# Sheet1.net
KiCad netlist of a schematic drawn in Altium Designer
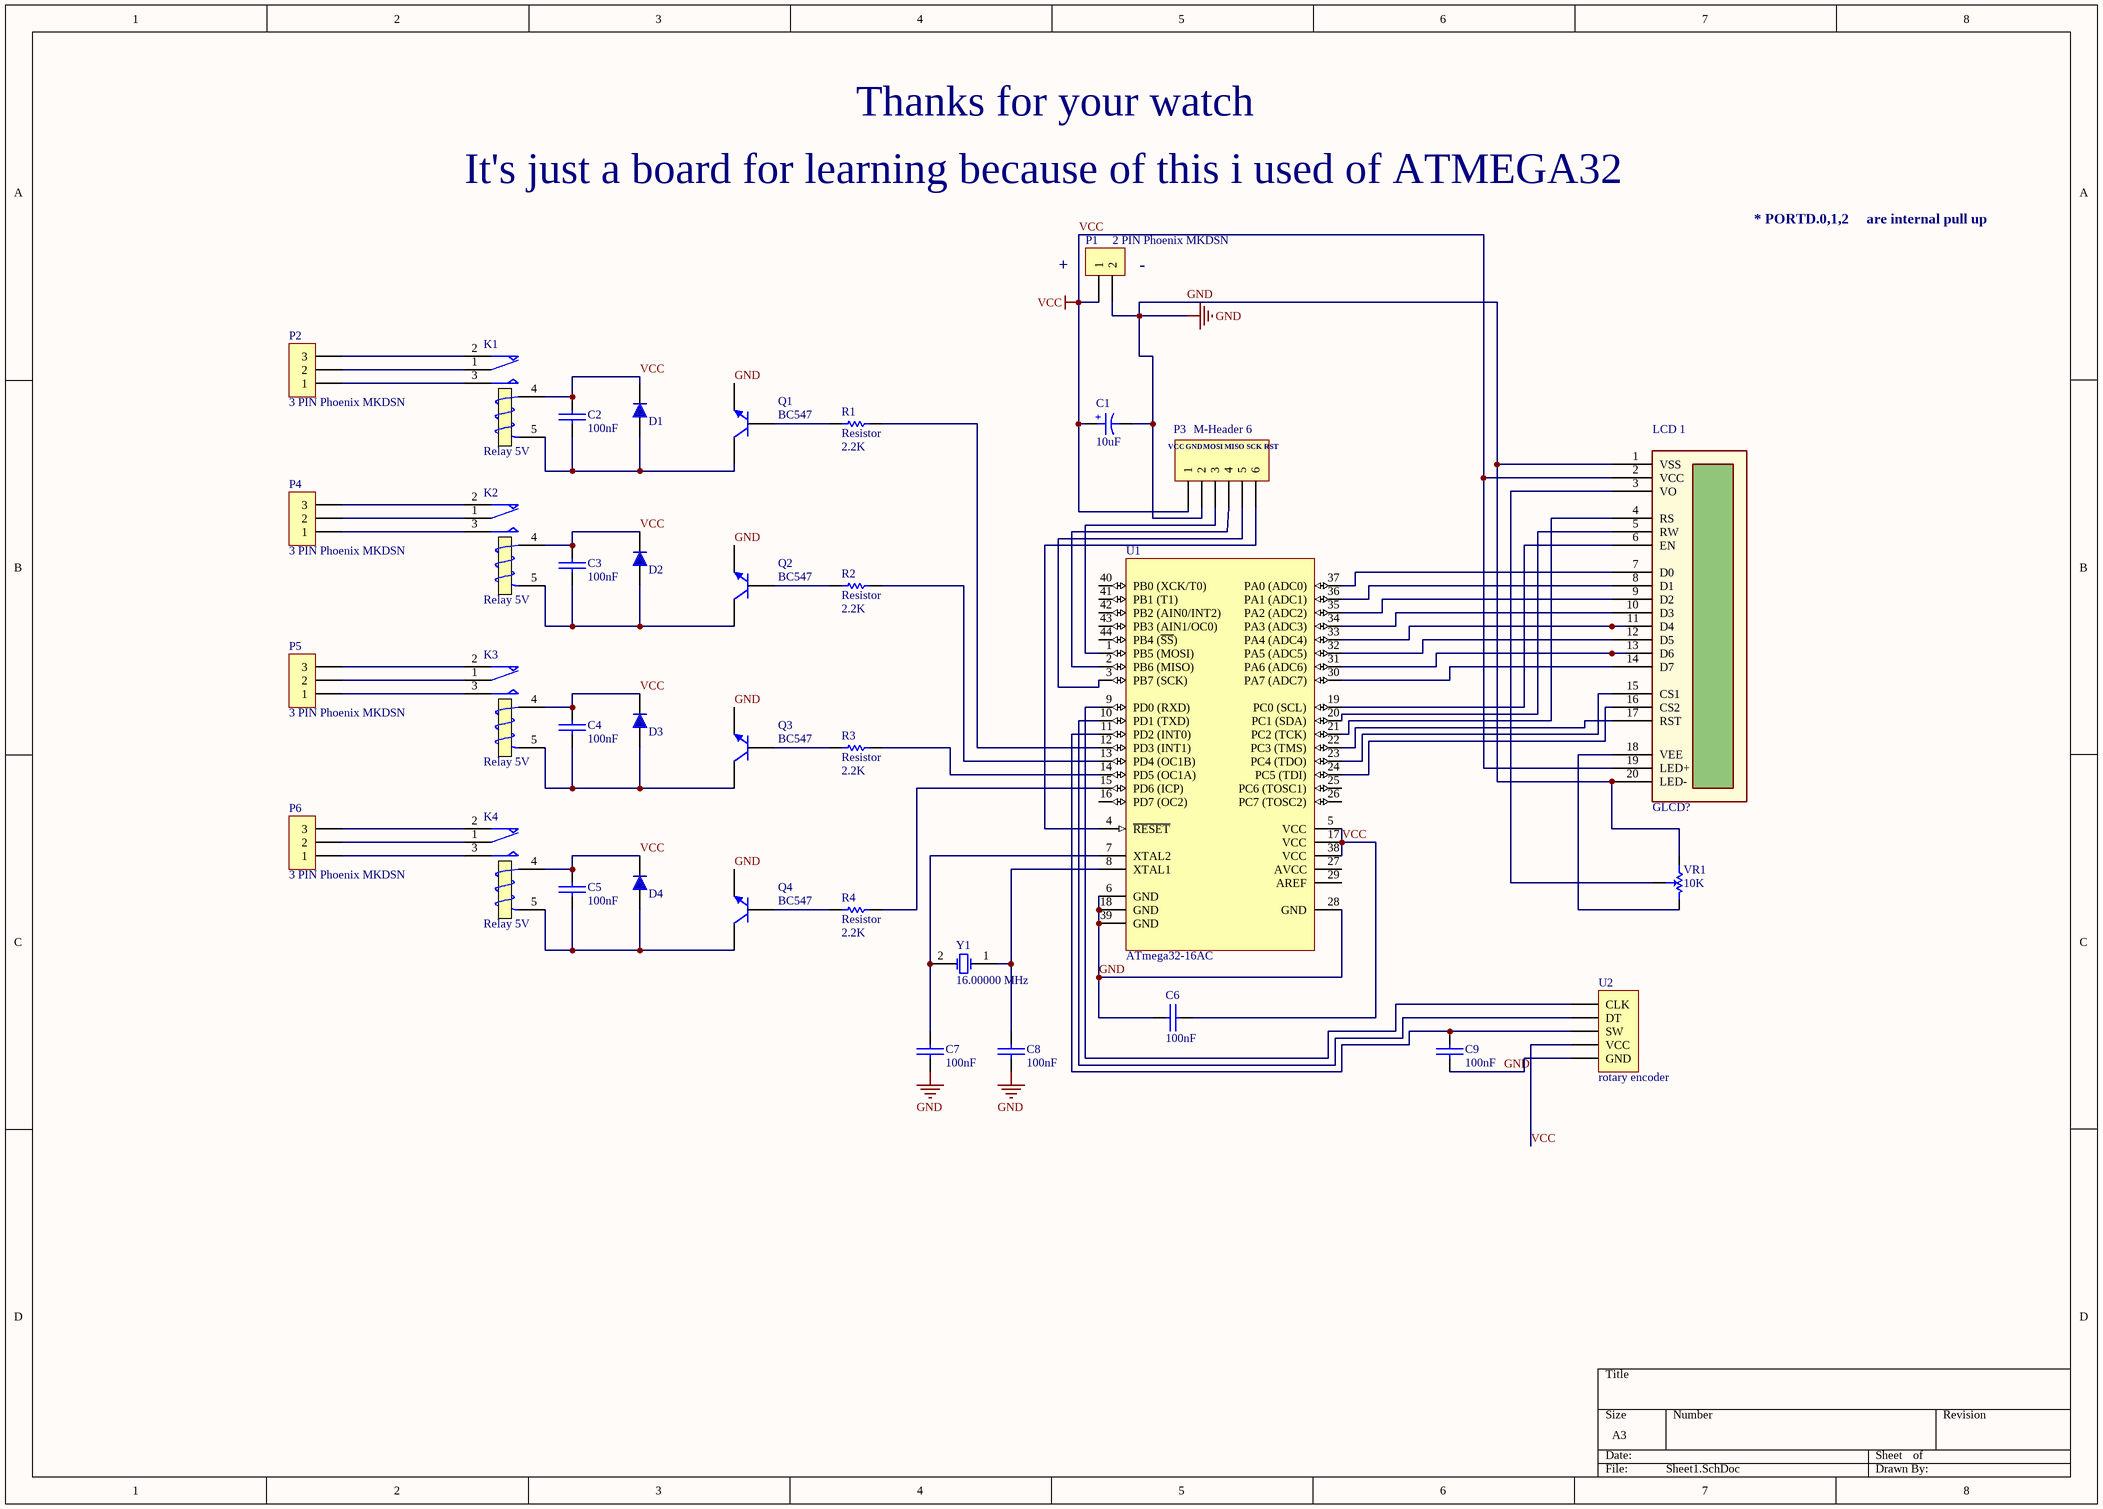
[diagram p0: Sheet1.SchDoc]

(export (version "E")
  (design (tool "Eeschema 10.0.6"))
  (components
    (comp (ref "C1")
      (value "10uF")
      (footprint "Cap 12.5x25-5")
      (description "Capacitor DIP")
      (libsource (lib "Inactive components") (part "Capacitor DIP"))
    )
    (comp (ref "C2")
      (value "100nF")
      (footprint "Cap - 100nF")
      (description "Bipolar Capacitor")
      (fields (field (name "VOLTAGE") "100V") (field (name "DESIGNER") "Saeid Jorablo"))
      (libsource (lib "My_Library") (part "Cap-Bipolar"))
    )
    (comp (ref "C3")
      (value "100nF")
      (footprint "Cap - 100nF")
      (description "Bipolar Capacitor")
      (fields (field (name "VOLTAGE") "100V") (field (name "DESIGNER") "Saeid Jorablo"))
      (libsource (lib "My_Library") (part "Cap-Bipolar"))
    )
    (comp (ref "C4")
      (value "100nF")
      (footprint "Cap - 100nF")
      (description "Bipolar Capacitor")
      (fields (field (name "VOLTAGE") "100V") (field (name "DESIGNER") "Saeid Jorablo"))
      (libsource (lib "My_Library") (part "Cap-Bipolar"))
    )
    (comp (ref "C5")
      (value "100nF")
      (footprint "Cap - 100nF")
      (description "Bipolar Capacitor")
      (fields (field (name "VOLTAGE") "100V") (field (name "DESIGNER") "Saeid Jorablo"))
      (libsource (lib "My_Library") (part "Cap-Bipolar"))
    )
    (comp (ref "C6")
      (value "100nF")
      (footprint "Cap - 100nF")
      (description "Bipolar Capacitor")
      (fields (field (name "VOLTAGE") "100V") (field (name "DESIGNER") "Saeid Jorablo"))
      (libsource (lib "My_Library") (part "Cap-Bipolar"))
    )
    (comp (ref "C7")
      (value "100nF")
      (footprint "Cap - 100nF")
      (description "Bipolar Capacitor")
      (fields (field (name "VOLTAGE") "100V") (field (name "DESIGNER") "Saeid Jorablo"))
      (libsource (lib "My_Library") (part "Cap-Bipolar"))
    )
    (comp (ref "C8")
      (value "100nF")
      (footprint "Cap - 100nF")
      (description "Bipolar Capacitor")
      (fields (field (name "VOLTAGE") "100V") (field (name "DESIGNER") "Saeid Jorablo"))
      (libsource (lib "My_Library") (part "Cap-Bipolar"))
    )
    (comp (ref "C9")
      (value "100nF")
      (footprint "Cap - 100nF")
      (description "Bipolar Capacitor")
      (fields (field (name "VOLTAGE") "100V") (field (name "DESIGNER") "Saeid Jorablo"))
      (libsource (lib "My_Library") (part "Cap-Bipolar"))
    )
    (comp (ref "D1")
      (value "1n4007")
      (footprint "Diode 1N4007 SMD")
      (description "Diode 1n4007")
      (libsource (lib "Semiconductors") (part "Diode 1n4007"))
    )
    (comp (ref "D2")
      (value "1n4007")
      (footprint "Diode 1N4007 SMD")
      (description "Diode 1n4007")
      (libsource (lib "Semiconductors") (part "Diode 1n4007"))
    )
    (comp (ref "D3")
      (value "1n4007")
      (footprint "Diode 1N4007 SMD")
      (description "Diode 1n4007")
      (libsource (lib "Semiconductors") (part "Diode 1n4007"))
    )
    (comp (ref "D4")
      (value "1n4007")
      (footprint "Diode 1N4007 SMD")
      (description "Diode 1n4007")
      (libsource (lib "Semiconductors") (part "Diode 1n4007"))
    )
    (comp (ref "K1")
      (value "Relay 5V")
      (footprint "Relay 15.40x12.10x13.10")
      (libsource (lib "Optoelectronics") (part "Relay 15.40x12.10x13.10"))
    )
    (comp (ref "K2")
      (value "Relay 5V")
      (footprint "Relay 15.40x12.10x13.10")
      (libsource (lib "Optoelectronics") (part "Relay 15.40x12.10x13.10"))
    )
    (comp (ref "K3")
      (value "Relay 5V")
      (footprint "Relay 15.40x12.10x13.10")
      (libsource (lib "Optoelectronics") (part "Relay 15.40x12.10x13.10"))
    )
    (comp (ref "K4")
      (value "Relay 5V")
      (footprint "Relay 15.40x12.10x13.10")
      (libsource (lib "Optoelectronics") (part "Relay 15.40x12.10x13.10"))
    )
    (comp (ref "LCD 1")
      (value "GLCD?")
      (footprint "LCD 128x64 graphic")
      (libsource (lib "Optoelectronics") (part "LCD 128x64 graphic"))
    )
    (comp (ref "P1")
      (value "2 PIN Phoenix MKDSN")
      (footprint "2 PIN Phoenix MKDSN")
      (libsource (lib "Connectors") (part "2 PIN Phoenix MKDSN"))
    )
    (comp (ref "P2")
      (value "3 PIN Phoenix MKDSN")
      (footprint "3 PIN Phoenix MKDSN")
      (libsource (lib "Connectors") (part "3 PIN Phoenix MKDSN"))
    )
    (comp (ref "P3")
      (value "M-Header 6")
      (footprint "M-Header 6")
      (libsource (lib "Connectors") (part "M-Header 6"))
    )
    (comp (ref "P4")
      (value "3 PIN Phoenix MKDSN")
      (footprint "3 PIN Phoenix MKDSN")
      (libsource (lib "Connectors") (part "3 PIN Phoenix MKDSN"))
    )
    (comp (ref "P5")
      (value "3 PIN Phoenix MKDSN")
      (footprint "3 PIN Phoenix MKDSN")
      (libsource (lib "Connectors") (part "3 PIN Phoenix MKDSN"))
    )
    (comp (ref "P6")
      (value "3 PIN Phoenix MKDSN")
      (footprint "3 PIN Phoenix MKDSN")
      (libsource (lib "Connectors") (part "3 PIN Phoenix MKDSN"))
    )
    (comp (ref "Q1")
      (value "BC547")
      (footprint "BC547 SMD SOT-23")
      (libsource (lib "Semiconductors") (part "BC547"))
    )
    (comp (ref "Q2")
      (value "BC547")
      (footprint "BC547 SMD SOT-23")
      (libsource (lib "Semiconductors") (part "BC547"))
    )
    (comp (ref "Q3")
      (value "BC547")
      (footprint "BC547 SMD SOT-23")
      (libsource (lib "Semiconductors") (part "BC547"))
    )
    (comp (ref "Q4")
      (value "BC547")
      (footprint "BC547 SMD SOT-23")
      (libsource (lib "Semiconductors") (part "BC547"))
    )
    (comp (ref "R1")
      (value "Resistor")
      (footprint "Resistor_SMD_1206 (3216)")
      (fields
        (field (name "ALTIUM_VALUE") "2.2K")
        (field (name "PUBLISHER") "Seyed Razi Vesali")
        (field (name "EMAIL") "razi.vesali@gmail.com")
      )
      (libsource (lib "Resistors") (part "Resistor"))
    )
    (comp (ref "R2")
      (value "Resistor")
      (footprint "Resistor_SMD_1206 (3216)")
      (fields
        (field (name "ALTIUM_VALUE") "2.2K")
        (field (name "PUBLISHER") "Seyed Razi Vesali")
        (field (name "EMAIL") "razi.vesali@gmail.com")
      )
      (libsource (lib "Resistors") (part "Resistor"))
    )
    (comp (ref "R3")
      (value "Resistor")
      (footprint "Resistor_SMD_1206 (3216)")
      (fields
        (field (name "ALTIUM_VALUE") "2.2K")
        (field (name "PUBLISHER") "Seyed Razi Vesali")
        (field (name "EMAIL") "razi.vesali@gmail.com")
      )
      (libsource (lib "Resistors") (part "Resistor"))
    )
    (comp (ref "R4")
      (value "Resistor")
      (footprint "Resistor_SMD_1206 (3216)")
      (fields
        (field (name "ALTIUM_VALUE") "2.2K")
        (field (name "PUBLISHER") "Seyed Razi Vesali")
        (field (name "EMAIL") "razi.vesali@gmail.com")
      )
      (libsource (lib "Resistors") (part "Resistor"))
    )
    (comp (ref "U1")
      (value "ATmega32-16AC")
      (footprint "44A")
      (description "8-Bit AVR Microcontroller with 32K Bytes of In-System Programmable Flash Memory")
      (fields (field (name "PUBLISHER") "Altium Limited"))
      (libsource (lib "Atmel Microcontroller 8-Bit AVR") (part "ATmega32-16AC"))
    )
    (comp (ref "U2")
      (value "rotary encoder")
      (footprint "rotary encoder")
      (libsource (lib "Modules") (part "rotary encoder"))
    )
    (comp (ref "VR1")
      (value "10K")
      (footprint "Multi Turn")
      (description "Multi Turn")
      (fields
        (field (name "PUBLISHER") "Seyed Razi vesali (SRV)")
        (field (name "EMAIL") "Razi.vesali@gmail.com")
      )
      (libsource (lib "Resistors") (part "Multi Turn"))
    )
    (comp (ref "Y1")
      (value "16.00000 MHz")
      (footprint "XTAL Small")
      (description "XTAL Crystal")
      (libsource (lib "My_Library") (part "XTAL"))
    )
  )
  (nets
    (net (code "1") (name "GND") (class "Default")
      (node (ref "C1") (pin "2") (pinfunction "2_2") (pintype "passive"))
      (node (ref "C6") (pin "1") (pinfunction "+_1") (pintype "passive"))
      (node (ref "C7") (pin "2") (pinfunction "-_2") (pintype "passive"))
      (node (ref "C8") (pin "2") (pinfunction "-_2") (pintype "passive"))
      (node (ref "C9") (pin "2") (pinfunction "-_2") (pintype "passive"))
      (node (ref "LCD 1") (pin "1") (pinfunction "VSS_1") (pintype "passive"))
      (node (ref "LCD 1") (pin "20") (pinfunction "LED-_20") (pintype "passive"))
      (node (ref "P1") (pin "2") (pinfunction "2_2") (pintype "passive"))
      (node (ref "P3") (pin "2") (pinfunction "2_2") (pintype "passive"))
      (node (ref "Q1") (pin "1") (pinfunction "E_1") (pintype "passive"))
      (node (ref "Q2") (pin "1") (pinfunction "E_1") (pintype "passive"))
      (node (ref "Q3") (pin "1") (pinfunction "E_1") (pintype "passive"))
      (node (ref "Q4") (pin "1") (pinfunction "E_1") (pintype "passive"))
      (node (ref "U1") (pin "18") (pinfunction "GND_18") (pintype "power_in"))
      (node (ref "U1") (pin "28") (pinfunction "GND_28") (pintype "power_in"))
      (node (ref "U1") (pin "39") (pinfunction "GND_39") (pintype "power_in"))
      (node (ref "U1") (pin "6") (pinfunction "GND_6") (pintype "power_in"))
      (node (ref "U2") (pin "5") (pinfunction "GND_5") (pintype "passive"))
      (node (ref "VR1") (pin "1") (pinfunction "CCW_1") (pintype "passive"))
    )
    (net (code "2") (name "Net-(C2-+)") (class "Default")
      (node (ref "C2") (pin "1") (pinfunction "+_1") (pintype "passive"))
      (node (ref "D1") (pin "1") (pintype "passive"))
      (node (ref "K1") (pin "5") (pinfunction "T2_5") (pintype "passive"))
      (node (ref "Q1") (pin "3") (pinfunction "C_3") (pintype "passive"))
    )
    (net (code "3") (name "Net-(C3-+)") (class "Default")
      (node (ref "C3") (pin "1") (pinfunction "+_1") (pintype "passive"))
      (node (ref "D2") (pin "1") (pintype "passive"))
      (node (ref "K2") (pin "5") (pinfunction "T2_5") (pintype "passive"))
      (node (ref "Q2") (pin "3") (pinfunction "C_3") (pintype "passive"))
    )
    (net (code "4") (name "Net-(C4-+)") (class "Default")
      (node (ref "C4") (pin "1") (pinfunction "+_1") (pintype "passive"))
      (node (ref "D3") (pin "1") (pintype "passive"))
      (node (ref "K3") (pin "5") (pinfunction "T2_5") (pintype "passive"))
      (node (ref "Q3") (pin "3") (pinfunction "C_3") (pintype "passive"))
    )
    (net (code "5") (name "Net-(C5-+)") (class "Default")
      (node (ref "C5") (pin "1") (pinfunction "+_1") (pintype "passive"))
      (node (ref "D4") (pin "1") (pintype "passive"))
      (node (ref "K4") (pin "5") (pinfunction "T2_5") (pintype "passive"))
      (node (ref "Q4") (pin "3") (pinfunction "C_3") (pintype "passive"))
    )
    (net (code "6") (name "Net-(C7-+)") (class "Default")
      (node (ref "C7") (pin "1") (pinfunction "+_1") (pintype "passive"))
      (node (ref "U1") (pin "7") (pinfunction "XTAL2_7") (pintype "passive"))
      (node (ref "Y1") (pin "2") (pinfunction "OSC2_2") (pintype "passive"))
    )
    (net (code "7") (name "Net-(C8-+)") (class "Default")
      (node (ref "C8") (pin "1") (pinfunction "+_1") (pintype "passive"))
      (node (ref "U1") (pin "8") (pinfunction "XTAL1_8") (pintype "passive"))
      (node (ref "Y1") (pin "1") (pinfunction "OSC1_1") (pintype "passive"))
    )
    (net (code "8") (name "Net-(C9-+)") (class "Default")
      (node (ref "C9") (pin "1") (pinfunction "+_1") (pintype "passive"))
      (node (ref "U1") (pin "11") (pinfunction "PD2_(INT0)_11") (pintype "bidirectional"))
      (node (ref "U2") (pin "3") (pinfunction "SW_3") (pintype "passive"))
    )
    (net (code "9") (name "Net-(K1-COM)") (class "Default")
      (node (ref "K1") (pin "1") (pinfunction "COM_1") (pintype "passive"))
      (node (ref "P2") (pin "2") (pinfunction "2_2") (pintype "passive"))
    )
    (net (code "10") (name "Net-(K1-NC)") (class "Default")
      (node (ref "K1") (pin "2") (pinfunction "NC_2") (pintype "passive"))
      (node (ref "P2") (pin "3") (pinfunction "3_3") (pintype "passive"))
    )
    (net (code "11") (name "Net-(K1-NO)") (class "Default")
      (node (ref "K1") (pin "3") (pinfunction "NO_3") (pintype "passive"))
      (node (ref "P2") (pin "1") (pinfunction "1_1") (pintype "passive"))
    )
    (net (code "12") (name "Net-(K2-COM)") (class "Default")
      (node (ref "K2") (pin "1") (pinfunction "COM_1") (pintype "passive"))
      (node (ref "P4") (pin "2") (pinfunction "2_2") (pintype "passive"))
    )
    (net (code "13") (name "Net-(K2-NC)") (class "Default")
      (node (ref "K2") (pin "2") (pinfunction "NC_2") (pintype "passive"))
      (node (ref "P4") (pin "3") (pinfunction "3_3") (pintype "passive"))
    )
    (net (code "14") (name "Net-(K2-NO)") (class "Default")
      (node (ref "K2") (pin "3") (pinfunction "NO_3") (pintype "passive"))
      (node (ref "P4") (pin "1") (pinfunction "1_1") (pintype "passive"))
    )
    (net (code "15") (name "Net-(K3-COM)") (class "Default")
      (node (ref "K3") (pin "1") (pinfunction "COM_1") (pintype "passive"))
      (node (ref "P5") (pin "2") (pinfunction "2_2") (pintype "passive"))
    )
    (net (code "16") (name "Net-(K3-NC)") (class "Default")
      (node (ref "K3") (pin "2") (pinfunction "NC_2") (pintype "passive"))
      (node (ref "P5") (pin "3") (pinfunction "3_3") (pintype "passive"))
    )
    (net (code "17") (name "Net-(K3-NO)") (class "Default")
      (node (ref "K3") (pin "3") (pinfunction "NO_3") (pintype "passive"))
      (node (ref "P5") (pin "1") (pinfunction "1_1") (pintype "passive"))
    )
    (net (code "18") (name "Net-(K4-COM)") (class "Default")
      (node (ref "K4") (pin "1") (pinfunction "COM_1") (pintype "passive"))
      (node (ref "P6") (pin "2") (pinfunction "2_2") (pintype "passive"))
    )
    (net (code "19") (name "Net-(K4-NC)") (class "Default")
      (node (ref "K4") (pin "2") (pinfunction "NC_2") (pintype "passive"))
      (node (ref "P6") (pin "3") (pinfunction "3_3") (pintype "passive"))
    )
    (net (code "20") (name "Net-(K4-NO)") (class "Default")
      (node (ref "K4") (pin "3") (pinfunction "NO_3") (pintype "passive"))
      (node (ref "P6") (pin "1") (pinfunction "1_1") (pintype "passive"))
    )
    (net (code "21") (name "Net-(LCD 1-CS1)") (class "Default")
      (node (ref "LCD 1") (pin "15") (pinfunction "CS1_15") (pintype "passive"))
      (node (ref "U1") (pin "23") (pinfunction "PC4_(TDO)_23") (pintype "bidirectional"))
    )
    (net (code "22") (name "Net-(LCD 1-CS2)") (class "Default")
      (node (ref "LCD 1") (pin "16") (pinfunction "CS2_16") (pintype "passive"))
      (node (ref "U1") (pin "24") (pinfunction "PC5_(TDI)_24") (pintype "bidirectional"))
    )
    (net (code "23") (name "Net-(LCD 1-D0)") (class "Default")
      (node (ref "LCD 1") (pin "7") (pinfunction "D0_7") (pintype "passive"))
      (node (ref "U1") (pin "37") (pinfunction "PA0_(ADC0)_37") (pintype "bidirectional"))
    )
    (net (code "24") (name "Net-(LCD 1-D1)") (class "Default")
      (node (ref "LCD 1") (pin "8") (pinfunction "D1_8") (pintype "passive"))
      (node (ref "U1") (pin "36") (pinfunction "PA1_(ADC1)_36") (pintype "bidirectional"))
    )
    (net (code "25") (name "Net-(LCD 1-D2)") (class "Default")
      (node (ref "LCD 1") (pin "9") (pinfunction "D2_9") (pintype "passive"))
      (node (ref "U1") (pin "35") (pinfunction "PA2_(ADC2)_35") (pintype "bidirectional"))
    )
    (net (code "26") (name "Net-(LCD 1-D3)") (class "Default")
      (node (ref "LCD 1") (pin "10") (pinfunction "D3_10") (pintype "passive"))
      (node (ref "U1") (pin "34") (pinfunction "PA3_(ADC3)_34") (pintype "bidirectional"))
    )
    (net (code "27") (name "Net-(LCD 1-D4)") (class "Default")
      (node (ref "LCD 1") (pin "11") (pinfunction "D4_11") (pintype "passive"))
      (node (ref "U1") (pin "33") (pinfunction "PA4_(ADC4)_33") (pintype "bidirectional"))
    )
    (net (code "28") (name "Net-(LCD 1-D5)") (class "Default")
      (node (ref "LCD 1") (pin "12") (pinfunction "D5_12") (pintype "passive"))
      (node (ref "U1") (pin "32") (pinfunction "PA5_(ADC5)_32") (pintype "bidirectional"))
    )
    (net (code "29") (name "Net-(LCD 1-D6)") (class "Default")
      (node (ref "LCD 1") (pin "13") (pinfunction "D6_13") (pintype "passive"))
      (node (ref "U1") (pin "31") (pinfunction "PA6_(ADC6)_31") (pintype "bidirectional"))
    )
    (net (code "30") (name "Net-(LCD 1-D7)") (class "Default")
      (node (ref "LCD 1") (pin "14") (pinfunction "D7_14") (pintype "passive"))
      (node (ref "U1") (pin "30") (pinfunction "PA7_(ADC7)_30") (pintype "bidirectional"))
    )
    (net (code "31") (name "Net-(LCD 1-EN)") (class "Default")
      (node (ref "LCD 1") (pin "6") (pinfunction "EN_6") (pintype "passive"))
      (node (ref "U1") (pin "19") (pinfunction "PC0_(SCL)_19") (pintype "bidirectional"))
    )
    (net (code "32") (name "Net-(LCD 1-RS)") (class "Default")
      (node (ref "LCD 1") (pin "4") (pinfunction "RS_4") (pintype "passive"))
      (node (ref "U1") (pin "21") (pinfunction "PC2_(TCK)_21") (pintype "bidirectional"))
    )
    (net (code "33") (name "Net-(LCD 1-RST)") (class "Default")
      (node (ref "LCD 1") (pin "17") (pinfunction "RST_17") (pintype "passive"))
      (node (ref "U1") (pin "22") (pinfunction "PC3_(TMS)_22") (pintype "bidirectional"))
    )
    (net (code "34") (name "Net-(LCD 1-RW)") (class "Default")
      (node (ref "LCD 1") (pin "5") (pinfunction "RW_5") (pintype "passive"))
      (node (ref "U1") (pin "20") (pinfunction "PC1_(SDA)_20") (pintype "bidirectional"))
    )
    (net (code "35") (name "Net-(LCD 1-VEE)") (class "Default")
      (node (ref "LCD 1") (pin "18") (pinfunction "VEE_18") (pintype "passive"))
      (node (ref "VR1") (pin "2") (pinfunction "CW_2") (pintype "passive"))
    )
    (net (code "36") (name "Net-(LCD 1-VO)") (class "Default")
      (node (ref "LCD 1") (pin "3") (pinfunction "VO_3") (pintype "passive"))
      (node (ref "VR1") (pin "3") (pinfunction "Setpoint_3") (pintype "passive"))
    )
    (net (code "37") (name "Net-(Q1-B)") (class "Default")
      (node (ref "Q1") (pin "2") (pinfunction "B_2") (pintype "passive"))
      (node (ref "R1") (pin "1") (pinfunction "1_1") (pintype "passive"))
    )
    (net (code "38") (name "Net-(Q2-B)") (class "Default")
      (node (ref "Q2") (pin "2") (pinfunction "B_2") (pintype "passive"))
      (node (ref "R2") (pin "1") (pinfunction "1_1") (pintype "passive"))
    )
    (net (code "39") (name "Net-(Q3-B)") (class "Default")
      (node (ref "Q3") (pin "2") (pinfunction "B_2") (pintype "passive"))
      (node (ref "R3") (pin "1") (pinfunction "1_1") (pintype "passive"))
    )
    (net (code "40") (name "Net-(Q4-B)") (class "Default")
      (node (ref "Q4") (pin "2") (pinfunction "B_2") (pintype "passive"))
      (node (ref "R4") (pin "1") (pinfunction "1_1") (pintype "passive"))
    )
    (net (code "41") (name "Net-(U1-PB5_(MOSI))") (class "Default")
      (node (ref "P3") (pin "3") (pinfunction "3_3") (pintype "passive"))
      (node (ref "U1") (pin "1") (pinfunction "PB5_(MOSI)_1") (pintype "bidirectional"))
    )
    (net (code "42") (name "Net-(U1-PB6_(MISO))") (class "Default")
      (node (ref "P3") (pin "4") (pinfunction "4_4") (pintype "passive"))
      (node (ref "U1") (pin "2") (pinfunction "PB6_(MISO)_2") (pintype "bidirectional"))
    )
    (net (code "43") (name "Net-(U1-PB7_(SCK))") (class "Default")
      (node (ref "P3") (pin "5") (pinfunction "5_5") (pintype "passive"))
      (node (ref "U1") (pin "3") (pinfunction "PB7_(SCK)_3") (pintype "bidirectional"))
    )
    (net (code "44") (name "Net-(U1-PD0_(RXD))") (class "Default")
      (node (ref "U1") (pin "9") (pinfunction "PD0_(RXD)_9") (pintype "bidirectional"))
      (node (ref "U2") (pin "1") (pinfunction "CLK_1") (pintype "passive"))
    )
    (net (code "45") (name "Net-(U1-PD1_(TXD))") (class "Default")
      (node (ref "U1") (pin "10") (pinfunction "PD1_(TXD)_10") (pintype "bidirectional"))
      (node (ref "U2") (pin "2") (pinfunction "DT_2") (pintype "passive"))
    )
    (net (code "46") (name "Net-(U1-PD3_(INT1))") (class "Default")
      (node (ref "R1") (pin "2") (pinfunction "2_2") (pintype "passive"))
      (node (ref "U1") (pin "12") (pinfunction "PD3_(INT1)_12") (pintype "bidirectional"))
    )
    (net (code "47") (name "Net-(U1-PD4_(OC1B))") (class "Default")
      (node (ref "R2") (pin "2") (pinfunction "2_2") (pintype "passive"))
      (node (ref "U1") (pin "13") (pinfunction "PD4_(OC1B)_13") (pintype "bidirectional"))
    )
    (net (code "48") (name "Net-(U1-PD5_(OC1A))") (class "Default")
      (node (ref "R3") (pin "2") (pinfunction "2_2") (pintype "passive"))
      (node (ref "U1") (pin "14") (pinfunction "PD5_(OC1A)_14") (pintype "bidirectional"))
    )
    (net (code "49") (name "Net-(U1-PD6_(ICP))") (class "Default")
      (node (ref "R4") (pin "2") (pinfunction "2_2") (pintype "passive"))
      (node (ref "U1") (pin "15") (pinfunction "PD6_(ICP)_15") (pintype "bidirectional"))
    )
    (net (code "50") (name "Net-(U1-~{RESET})") (class "Default")
      (node (ref "P3") (pin "6") (pinfunction "6_6") (pintype "passive"))
      (node (ref "U1") (pin "4") (pinfunction "~{RESET}_4") (pintype "input"))
    )
    (net (code "51") (name "VCC") (class "Default")
      (node (ref "C1") (pin "1") (pinfunction "1_1") (pintype "passive"))
      (node (ref "C2") (pin "2") (pinfunction "-_2") (pintype "passive"))
      (node (ref "C3") (pin "2") (pinfunction "-_2") (pintype "passive"))
      (node (ref "C4") (pin "2") (pinfunction "-_2") (pintype "passive"))
      (node (ref "C5") (pin "2") (pinfunction "-_2") (pintype "passive"))
      (node (ref "C6") (pin "2") (pinfunction "-_2") (pintype "passive"))
      (node (ref "D1") (pin "2") (pintype "passive"))
      (node (ref "D2") (pin "2") (pintype "passive"))
      (node (ref "D3") (pin "2") (pintype "passive"))
      (node (ref "D4") (pin "2") (pintype "passive"))
      (node (ref "K1") (pin "4") (pinfunction "T1_4") (pintype "passive"))
      (node (ref "K2") (pin "4") (pinfunction "T1_4") (pintype "passive"))
      (node (ref "K3") (pin "4") (pinfunction "T1_4") (pintype "passive"))
      (node (ref "K4") (pin "4") (pinfunction "T1_4") (pintype "passive"))
      (node (ref "LCD 1") (pin "19") (pinfunction "LED+_19") (pintype "passive"))
      (node (ref "LCD 1") (pin "2") (pinfunction "VCC_2") (pintype "passive"))
      (node (ref "P1") (pin "1") (pinfunction "1_1") (pintype "passive"))
      (node (ref "P3") (pin "1") (pinfunction "1_1") (pintype "passive"))
      (node (ref "U1") (pin "17") (pinfunction "VCC_17") (pintype "power_in"))
      (node (ref "U1") (pin "38") (pinfunction "VCC_38") (pintype "power_in"))
      (node (ref "U1") (pin "5") (pinfunction "VCC_5") (pintype "power_in"))
      (node (ref "U2") (pin "4") (pinfunction "VCC_4") (pintype "passive"))
    )
    (net (code "52") (name "unconnected-(U1-AREF-Pad29)") (class "Default")
      (node (ref "U1") (pin "29") (pinfunction "AREF_29") (pintype "passive"))
    )
    (net (code "53") (name "unconnected-(U1-AVCC-Pad27)") (class "Default")
      (node (ref "U1") (pin "27") (pinfunction "AVCC_27") (pintype "power_in"))
    )
    (net (code "54") (name "unconnected-(U1-PB0_(XCK{slash}T0)-Pad40)") (class "Default")
      (node (ref "U1") (pin "40") (pinfunction "PB0_(XCK/T0)_40") (pintype "bidirectional"))
    )
    (net (code "55") (name "unconnected-(U1-PB1_(T1)-Pad41)") (class "Default")
      (node (ref "U1") (pin "41") (pinfunction "PB1_(T1)_41") (pintype "bidirectional"))
    )
    (net (code "56") (name "unconnected-(U1-PB2_(AIN0{slash}INT2)-Pad42)") (class "Default")
      (node (ref "U1") (pin "42") (pinfunction "PB2_(AIN0/INT2)_42") (pintype "bidirectional"))
    )
    (net (code "57") (name "unconnected-(U1-PB3_(AIN1{slash}OC0)-Pad43)") (class "Default")
      (node (ref "U1") (pin "43") (pinfunction "PB3_(AIN1/OC0)_43") (pintype "bidirectional"))
    )
    (net (code "58") (name "unconnected-(U1-PB4_(~{SS})-Pad44)") (class "Default")
      (node (ref "U1") (pin "44") (pinfunction "PB4_(~{SS})_44") (pintype "bidirectional"))
    )
    (net (code "59") (name "unconnected-(U1-PC6_(TOSC1)-Pad25)") (class "Default")
      (node (ref "U1") (pin "25") (pinfunction "PC6_(TOSC1)_25") (pintype "bidirectional"))
    )
    (net (code "60") (name "unconnected-(U1-PC7_(TOSC2)-Pad26)") (class "Default")
      (node (ref "U1") (pin "26") (pinfunction "PC7_(TOSC2)_26") (pintype "bidirectional"))
    )
    (net (code "61") (name "unconnected-(U1-PD7_(OC2)-Pad16)") (class "Default")
      (node (ref "U1") (pin "16") (pinfunction "PD7_(OC2)_16") (pintype "bidirectional"))
    )
  )
)
